# i-ching_2020-06-26_19-34-40.net
KiCad netlist of a schematic drawn in EasyEDA
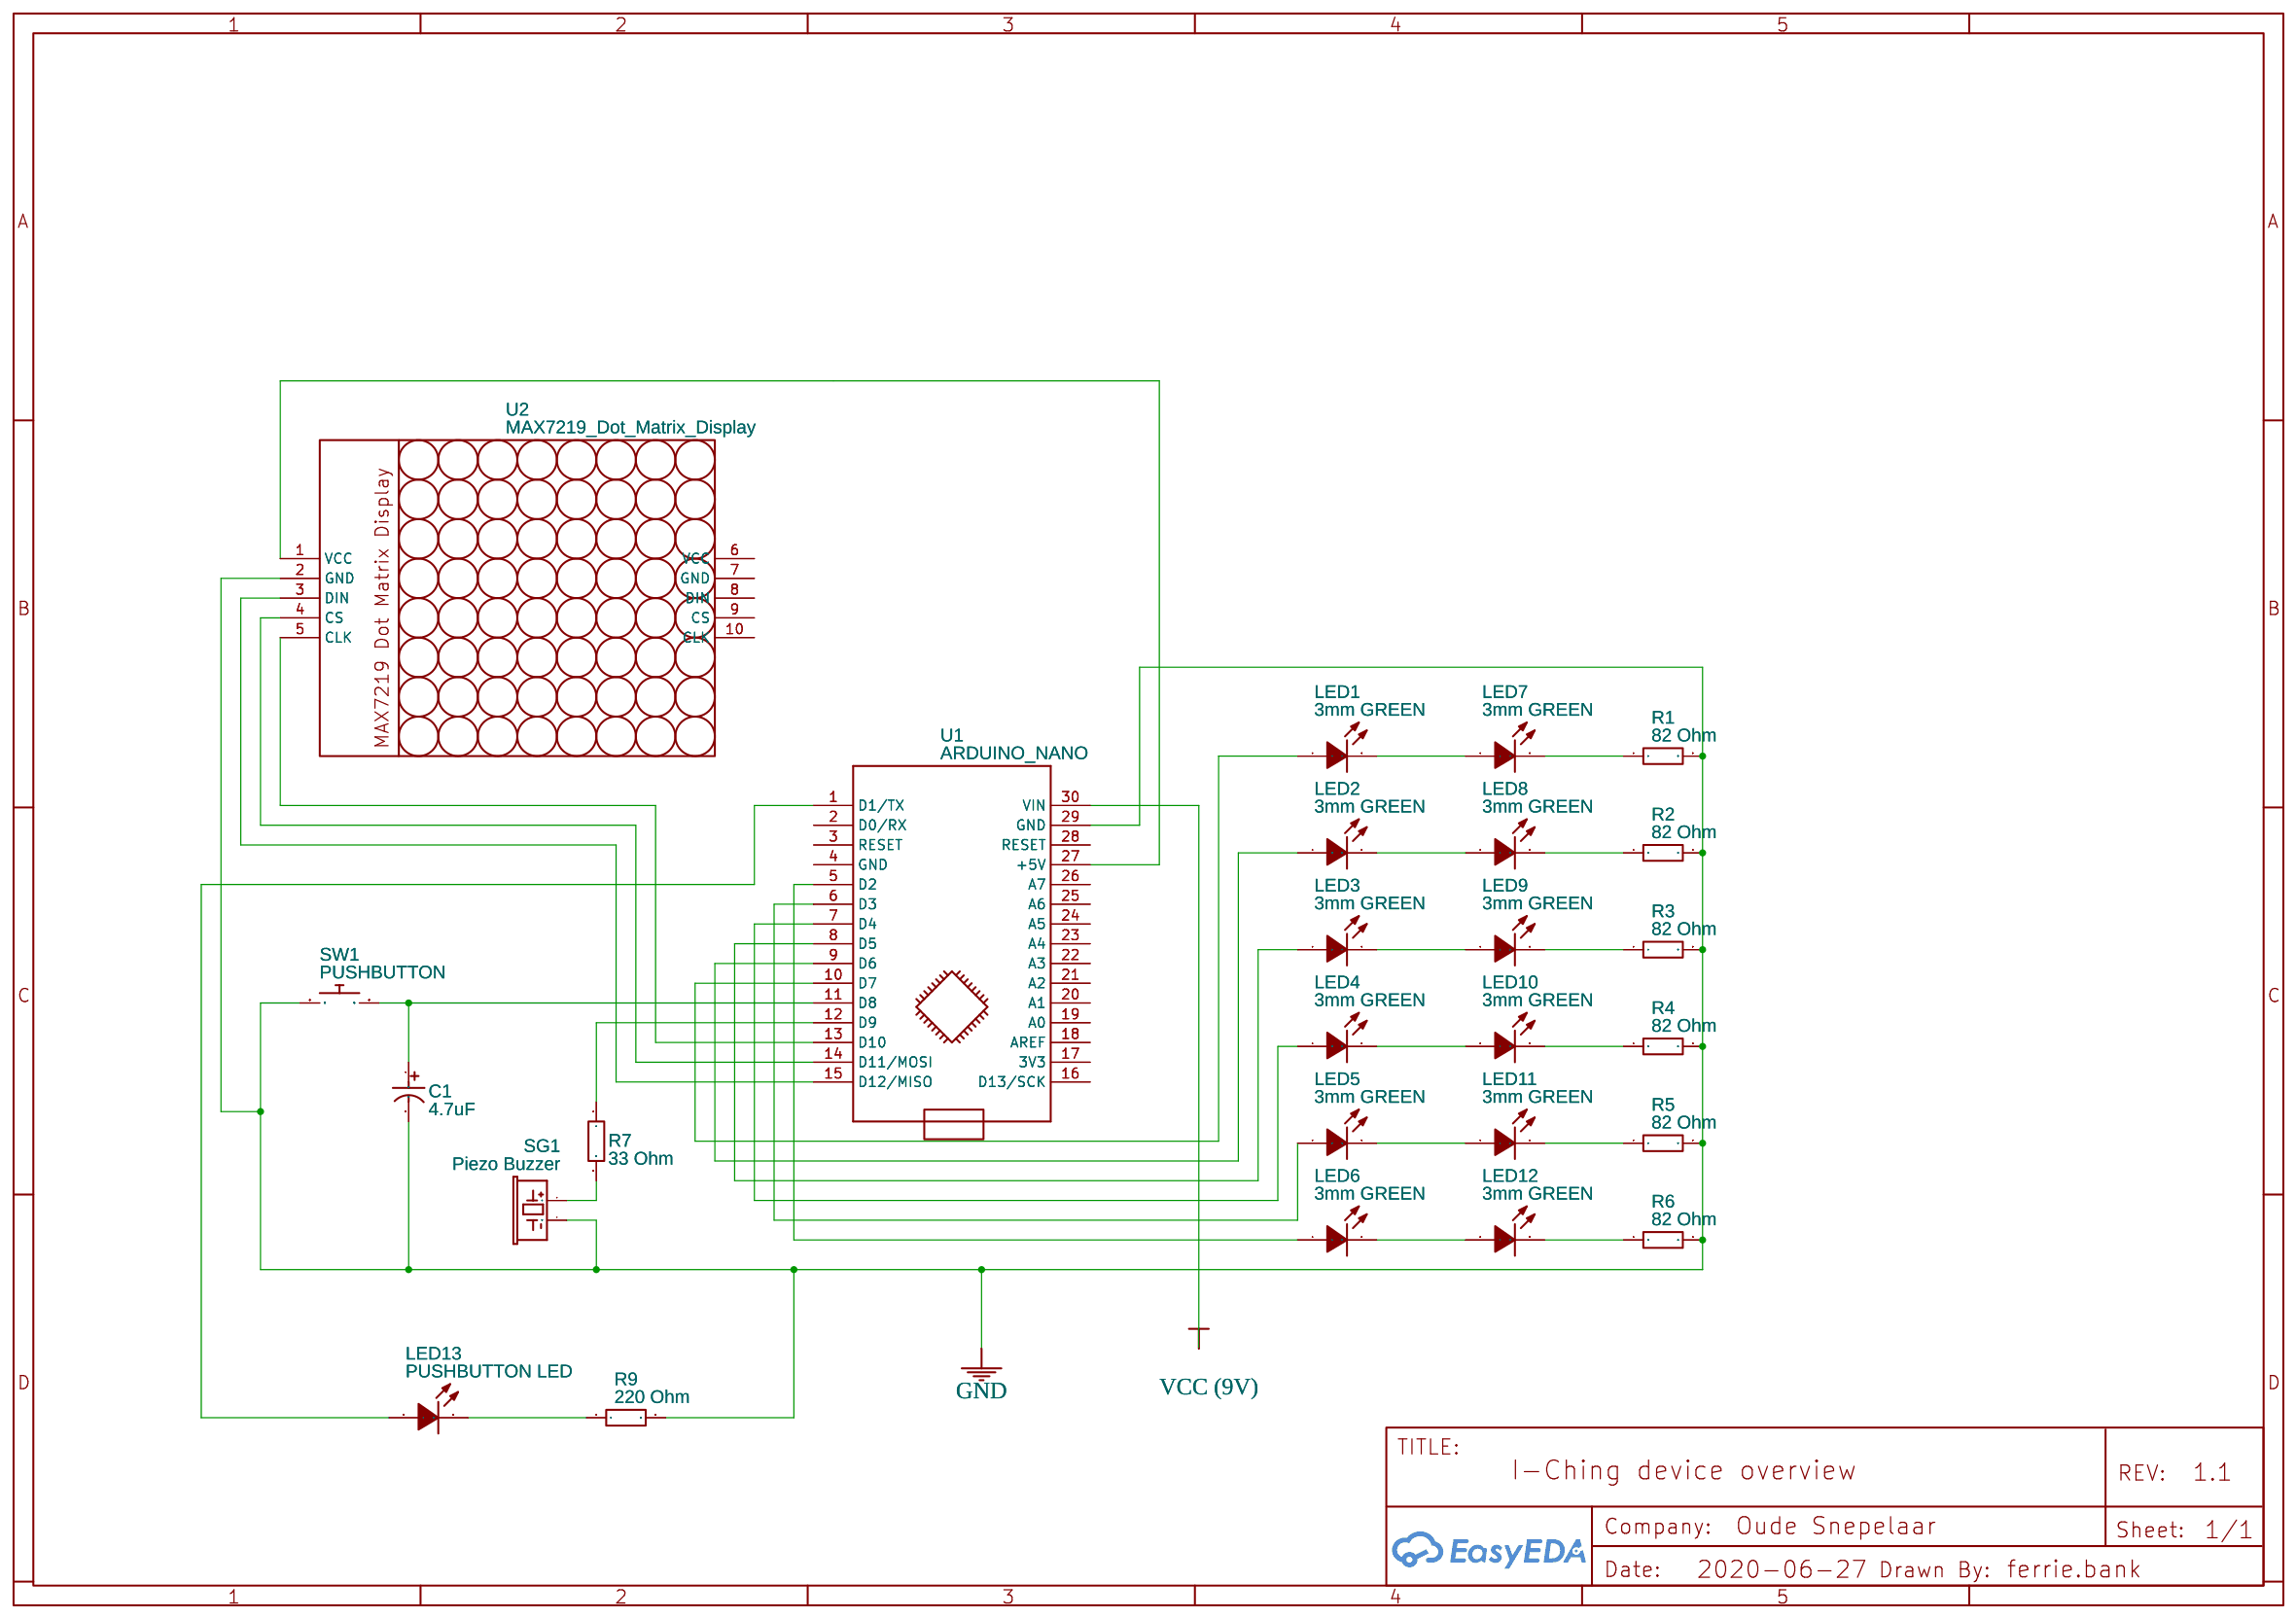
[diagram p0: I-Ching device overview]
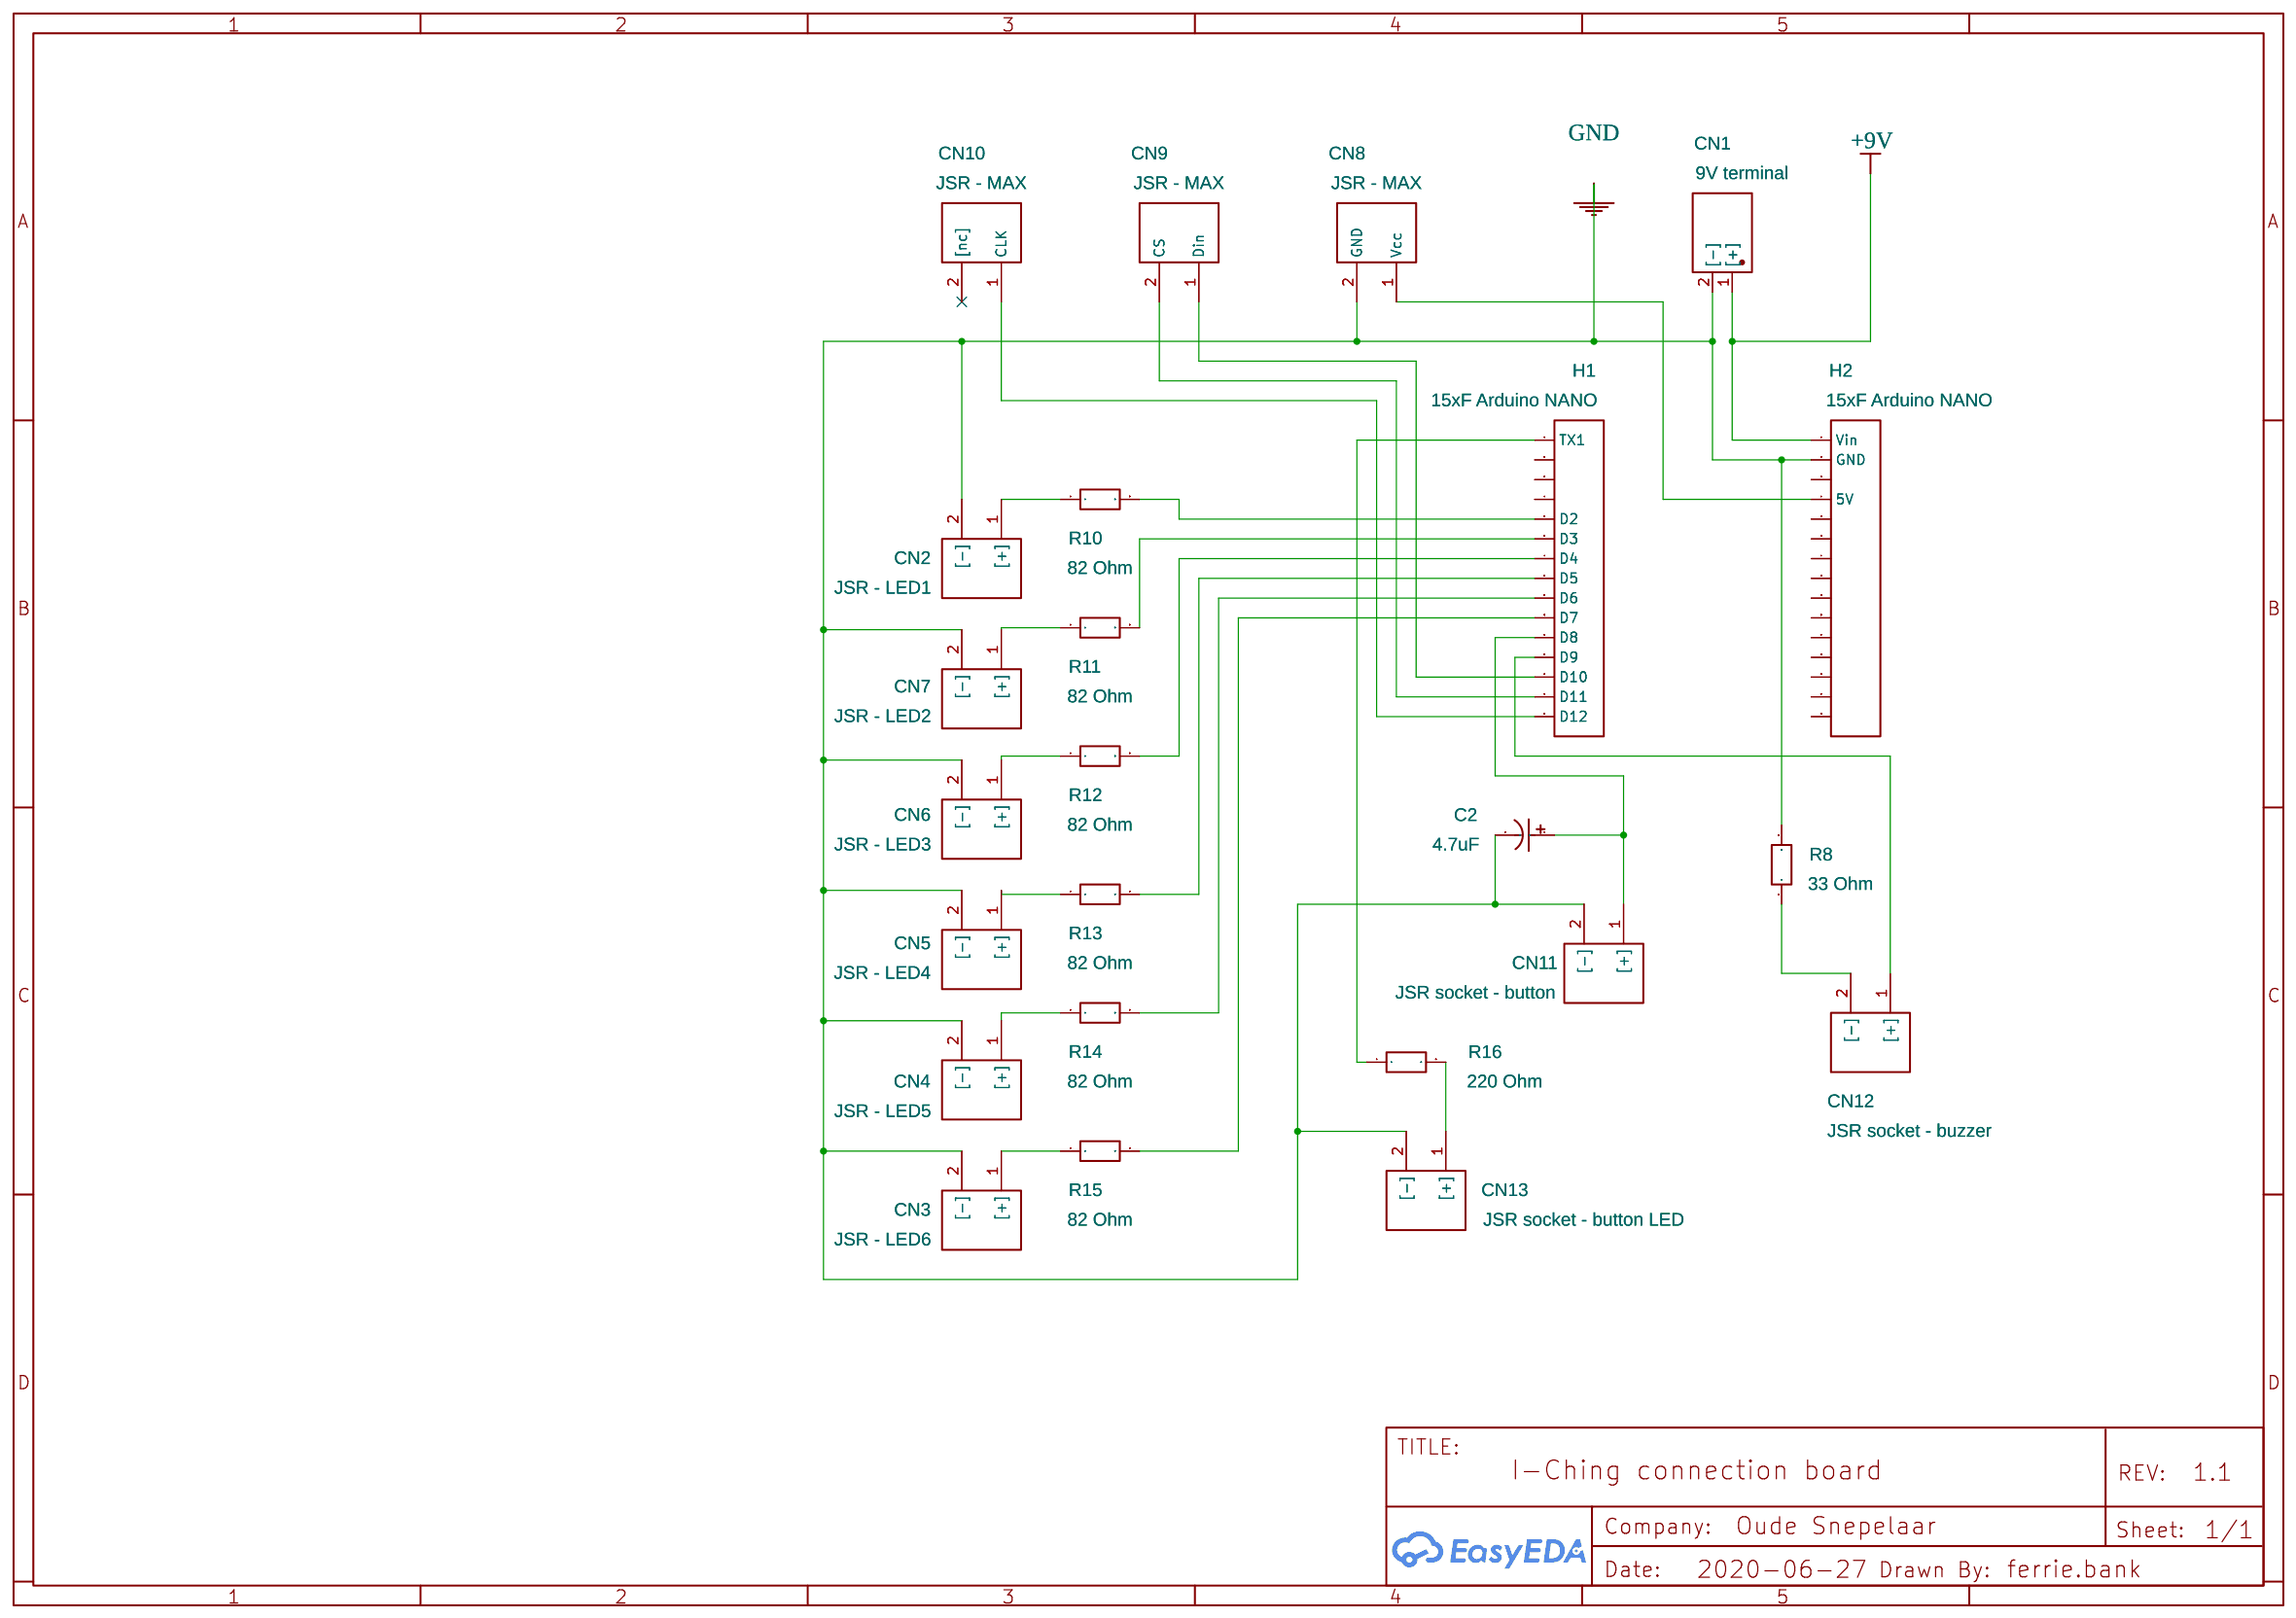
[diagram p1: I-Ching connection board]

(export (version "E")
  (design (tool "Eeschema 10.0.6"))
  (components
    (comp (ref "C1")
      (value "4.7uF")
      (fields (field (name "BOM_Manufacturer Part") "0.1UF 50V") (field (name "BOM_Supplier Part") "C28061"))
      (libsource (lib "") (part "0.1UF 50V"))
    )
    (comp (ref "LED1")
      (value "3mm GREEN")
      (fields (field (name "BOM_Manufacturer Part") "3ARG4HWC") (field (name "BOM_Supplier Part") "C55640"))
      (libsource (lib "") (part "3ARG4HWC"))
    )
    (comp (ref "LED2")
      (value "3mm GREEN")
      (fields (field (name "BOM_Manufacturer Part") "3ARG4HWC") (field (name "BOM_Supplier Part") "C55640"))
      (libsource (lib "") (part "3ARG4HWC"))
    )
    (comp (ref "LED3")
      (value "3mm GREEN")
      (fields (field (name "BOM_Manufacturer Part") "3ARG4HWC") (field (name "BOM_Supplier Part") "C55640"))
      (libsource (lib "") (part "3ARG4HWC"))
    )
    (comp (ref "LED4")
      (value "3mm GREEN")
      (fields (field (name "BOM_Manufacturer Part") "3ARG4HWC") (field (name "BOM_Supplier Part") "C55640"))
      (libsource (lib "") (part "3ARG4HWC"))
    )
    (comp (ref "LED5")
      (value "3mm GREEN")
      (fields (field (name "BOM_Manufacturer Part") "3ARG4HWC") (field (name "BOM_Supplier Part") "C55640"))
      (libsource (lib "") (part "3ARG4HWC"))
    )
    (comp (ref "LED6")
      (value "3mm GREEN")
      (fields (field (name "BOM_Manufacturer Part") "3ARG4HWC") (field (name "BOM_Supplier Part") "C55640"))
      (libsource (lib "") (part "3ARG4HWC"))
    )
    (comp (ref "LED7")
      (value "3mm GREEN")
      (fields (field (name "BOM_Manufacturer Part") "3ARG4HWC") (field (name "BOM_Supplier Part") "C55640"))
      (libsource (lib "") (part "3ARG4HWC"))
    )
    (comp (ref "LED8")
      (value "3mm GREEN")
      (fields (field (name "BOM_Manufacturer Part") "3ARG4HWC") (field (name "BOM_Supplier Part") "C55640"))
      (libsource (lib "") (part "3ARG4HWC"))
    )
    (comp (ref "LED9")
      (value "3mm GREEN")
      (fields (field (name "BOM_Manufacturer Part") "3ARG4HWC") (field (name "BOM_Supplier Part") "C55640"))
      (libsource (lib "") (part "3ARG4HWC"))
    )
    (comp (ref "LED10")
      (value "3mm GREEN")
      (fields (field (name "BOM_Manufacturer Part") "3ARG4HWC") (field (name "BOM_Supplier Part") "C55640"))
      (libsource (lib "") (part "3ARG4HWC"))
    )
    (comp (ref "LED11")
      (value "3mm GREEN")
      (fields (field (name "BOM_Manufacturer Part") "3ARG4HWC") (field (name "BOM_Supplier Part") "C55640"))
      (libsource (lib "") (part "3ARG4HWC"))
    )
    (comp (ref "LED12")
      (value "3mm GREEN")
      (fields (field (name "BOM_Manufacturer Part") "3ARG4HWC") (field (name "BOM_Supplier Part") "C55640"))
      (libsource (lib "") (part "3ARG4HWC"))
    )
    (comp (ref "LED13")
      (value "PUSHBUTTON LED")
      (fields (field (name "BOM_Manufacturer Part") "3ARG4HWC") (field (name "BOM_Supplier Part") "C55640"))
      (libsource (lib "") (part "3ARG4HWC"))
    )
    (comp (ref "R1")
      (value "82 Ohm")
      (fields
        (field (name "BOM_Manufacturer Part") "MFR2WSJT-73-220R")
        (field (name "BOM_Supplier Part") "C176568")
      )
      (libsource (lib "") (part "MFR2WSJT-73-220R_1"))
    )
    (comp (ref "R2")
      (value "82 Ohm")
      (fields
        (field (name "BOM_Manufacturer Part") "MFR2WSJT-73-220R")
        (field (name "BOM_Supplier Part") "C176568")
      )
      (libsource (lib "") (part "MFR2WSJT-73-220R_1"))
    )
    (comp (ref "R3")
      (value "82 Ohm")
      (fields
        (field (name "BOM_Manufacturer Part") "MFR2WSJT-73-220R")
        (field (name "BOM_Supplier Part") "C176568")
      )
      (libsource (lib "") (part "MFR2WSJT-73-220R_1"))
    )
    (comp (ref "R4")
      (value "82 Ohm")
      (fields
        (field (name "BOM_Manufacturer Part") "MFR2WSJT-73-220R")
        (field (name "BOM_Supplier Part") "C176568")
      )
      (libsource (lib "") (part "MFR2WSJT-73-220R_1"))
    )
    (comp (ref "R5")
      (value "82 Ohm")
      (fields
        (field (name "BOM_Manufacturer Part") "MFR2WSJT-73-220R")
        (field (name "BOM_Supplier Part") "C176568")
      )
      (libsource (lib "") (part "MFR2WSJT-73-220R_1"))
    )
    (comp (ref "R6")
      (value "82 Ohm")
      (fields
        (field (name "BOM_Manufacturer Part") "MFR2WSJT-73-220R")
        (field (name "BOM_Supplier Part") "C176568")
      )
      (libsource (lib "") (part "MFR2WSJT-73-220R_1"))
    )
    (comp (ref "R7")
      (value "33 Ohm")
      (fields
        (field (name "BOM_Manufacturer Part") "MFR2WSJT-73-220R")
        (field (name "BOM_Supplier Part") "C176568")
      )
      (libsource (lib "") (part "MFR2WSJT-73-220R"))
    )
    (comp (ref "R9")
      (value "220 Ohm")
      (fields
        (field (name "BOM_Manufacturer Part") "MFR2WSJT-73-220R")
        (field (name "BOM_Supplier Part") "C176568")
      )
      (libsource (lib "") (part "MFR2WSJT-73-220R_1"))
    )
    (comp (ref "SG1") (value "Piezo Buzzer") (libsource (lib "") (part "Piezo Buzzer")))
    (comp (ref "SW1") (value "PUSHBUTTON") (libsource (lib "") (part "SWITCH_PUSHBUTTONCK_KSS")))
    (comp (ref "U1") (value "ARDUINO_NANO") (libsource (lib "") (part "ARDUINO_NANO")))
    (comp (ref "U2")
      (value "MAX7219_Dot_Matrix_Display")
      (libsource (lib "") (part "MAX7219_Dot_Matrix_Display"))
    )
    (comp (ref "C2")
      (value "4.7uF")
      (fields (field (name "BOM_Manufacturer Part") "0.1UF 50V") (field (name "BOM_Supplier Part") "C28061"))
      (libsource (lib "") (part "0.1UF 50V"))
    )
    (comp (ref "CN1")
      (value "9V terminal")
      (fields (field (name "BOM_Manufacturer Part") "PA002-2P") (field (name "BOM_Supplier Part") "C163148"))
      (libsource (lib "") (part "PA002-2P"))
    )
    (comp (ref "CN2")
      (value "JSR - LED1")
      (fields
        (field (name "BOM_Manufacturer Part") "socket.blue5566-2Aneedle")
        (field (name "BOM_Supplier Part") "C62133")
      )
      (libsource (lib "") (part "socket.blue5566-2Aneedle_1"))
    )
    (comp (ref "CN3")
      (value "JSR - LED6")
      (fields
        (field (name "BOM_Manufacturer Part") "socket.blue5566-2Aneedle")
        (field (name "BOM_Supplier Part") "C62133")
      )
      (libsource (lib "") (part "socket.blue5566-2Aneedle_1"))
    )
    (comp (ref "CN4")
      (value "JSR - LED5")
      (fields
        (field (name "BOM_Manufacturer Part") "socket.blue5566-2Aneedle")
        (field (name "BOM_Supplier Part") "C62133")
      )
      (libsource (lib "") (part "socket.blue5566-2Aneedle_1"))
    )
    (comp (ref "CN5")
      (value "JSR - LED4")
      (fields
        (field (name "BOM_Manufacturer Part") "socket.blue5566-2Aneedle")
        (field (name "BOM_Supplier Part") "C62133")
      )
      (libsource (lib "") (part "socket.blue5566-2Aneedle_1"))
    )
    (comp (ref "CN6")
      (value "JSR - LED3")
      (fields
        (field (name "BOM_Manufacturer Part") "socket.blue5566-2Aneedle")
        (field (name "BOM_Supplier Part") "C62133")
      )
      (libsource (lib "") (part "socket.blue5566-2Aneedle_1"))
    )
    (comp (ref "CN7")
      (value "JSR - LED2")
      (fields
        (field (name "BOM_Manufacturer Part") "socket.blue5566-2Aneedle")
        (field (name "BOM_Supplier Part") "C62133")
      )
      (libsource (lib "") (part "socket.blue5566-2Aneedle_1"))
    )
    (comp (ref "CN8")
      (value "JSR - MAX")
      (fields
        (field (name "BOM_Manufacturer Part") "socket.blue5566-2Aneedle")
        (field (name "BOM_Supplier Part") "C62133")
      )
      (libsource (lib "") (part "socket.blue5566-2Aneedle_3"))
    )
    (comp (ref "CN9")
      (value "JSR - MAX")
      (fields
        (field (name "BOM_Manufacturer Part") "socket.blue5566-2Aneedle")
        (field (name "BOM_Supplier Part") "C62133")
      )
      (libsource (lib "") (part "socket.blue5566-2Aneedle_2"))
    )
    (comp (ref "CN10")
      (value "JSR - MAX")
      (fields
        (field (name "BOM_Manufacturer Part") "socket.blue5566-2Aneedle")
        (field (name "BOM_Supplier Part") "C62133")
      )
      (libsource (lib "") (part "socket.blue5566-2Aneedle"))
    )
    (comp (ref "CN11")
      (value "JSR socket - button")
      (fields
        (field (name "BOM_Manufacturer Part") "socket.blue5566-2Aneedle")
        (field (name "BOM_Supplier Part") "C62133")
      )
      (libsource (lib "") (part "socket.blue5566-2Aneedle_1"))
    )
    (comp (ref "CN12")
      (value "JSR socket - buzzer")
      (fields
        (field (name "BOM_Manufacturer Part") "socket.blue5566-2Aneedle")
        (field (name "BOM_Supplier Part") "C62133")
      )
      (libsource (lib "") (part "socket.blue5566-2Aneedle_1"))
    )
    (comp (ref "CN13")
      (value "JSR socket - button LED")
      (fields
        (field (name "BOM_Manufacturer Part") "socket.blue5566-2Aneedle")
        (field (name "BOM_Supplier Part") "C62133")
      )
      (libsource (lib "") (part "socket.blue5566-2Aneedle_1"))
    )
    (comp (ref "H1")
      (value "15xF Arduino NANO")
      (fields
        (field (name "BOM_Manufacturer Part") "220S-1*15P H=8.5MM Ytype Gold-plated")
        (field (name "BOM_Supplier Part") "C124408")
      )
      (libsource (lib "") (part "Header-Female-2.54_1x15"))
    )
    (comp (ref "H2")
      (value "15xF Arduino NANO")
      (fields
        (field (name "BOM_Manufacturer Part") "220S-1*15P H=8.5MM Ytype Gold-plated")
        (field (name "BOM_Supplier Part") "C124408")
      )
      (libsource (lib "") (part "Header-Female-2.54_1x15_1"))
    )
    (comp (ref "R8")
      (value "33 Ohm")
      (fields
        (field (name "BOM_Manufacturer Part") "RN 2WS 1K F T/B A1")
        (field (name "BOM_Supplier Part") "C433624")
      )
      (libsource (lib "") (part "RN 2WS 1K F T/B A1_C433624_1"))
    )
    (comp (ref "R10")
      (value "82 Ohm")
      (fields
        (field (name "BOM_Manufacturer Part") "RN 2WS 1K F T/B A1")
        (field (name "BOM_Supplier Part") "C433624")
      )
      (libsource (lib "") (part "RN 2WS 1K F T/B A1_C433624"))
    )
    (comp (ref "R11")
      (value "82 Ohm")
      (fields
        (field (name "BOM_Manufacturer Part") "RN 2WS 1K F T/B A1")
        (field (name "BOM_Supplier Part") "C433624")
      )
      (libsource (lib "") (part "RN 2WS 1K F T/B A1_C433624"))
    )
    (comp (ref "R12")
      (value "82 Ohm")
      (fields
        (field (name "BOM_Manufacturer Part") "RN 2WS 1K F T/B A1")
        (field (name "BOM_Supplier Part") "C433624")
      )
      (libsource (lib "") (part "RN 2WS 1K F T/B A1_C433624"))
    )
    (comp (ref "R13")
      (value "82 Ohm")
      (fields
        (field (name "BOM_Manufacturer Part") "RN 2WS 1K F T/B A1")
        (field (name "BOM_Supplier Part") "C433624")
      )
      (libsource (lib "") (part "RN 2WS 1K F T/B A1_C433624"))
    )
    (comp (ref "R14")
      (value "82 Ohm")
      (fields
        (field (name "BOM_Manufacturer Part") "RN 2WS 1K F T/B A1")
        (field (name "BOM_Supplier Part") "C433624")
      )
      (libsource (lib "") (part "RN 2WS 1K F T/B A1_C433624"))
    )
    (comp (ref "R15")
      (value "82 Ohm")
      (fields
        (field (name "BOM_Manufacturer Part") "RN 2WS 1K F T/B A1")
        (field (name "BOM_Supplier Part") "C433624")
      )
      (libsource (lib "") (part "RN 2WS 1K F T/B A1_C433624"))
    )
    (comp (ref "R16")
      (value "220 Ohm")
      (fields
        (field (name "BOM_Manufacturer Part") "RN 2WS 1K F T/B A1")
        (field (name "BOM_Supplier Part") "C433624")
      )
      (libsource (lib "") (part "RN 2WS 1K F T/B A1_C433624"))
    )
  )
  (nets
    (net (code "1") (name "+9V") (class "Default")
      (node (ref "CN1") (pin "1") (pinfunction "[+]_1") (pintype "unspecified"))
      (node (ref "H2") (pin "1") (pinfunction "Vin_1") (pintype "unspecified"))
    )
    (net (code "2") (name "GND") (class "Default")
      (node (ref "C1") (pin "2") (pinfunction "2_2") (pintype "input"))
      (node (ref "C2") (pin "2") (pinfunction "2_2") (pintype "input"))
      (node (ref "CN1") (pin "2") (pinfunction "[-]_2") (pintype "unspecified"))
      (node (ref "CN11") (pin "2") (pinfunction "[-]_2") (pintype "unspecified"))
      (node (ref "CN13") (pin "2") (pinfunction "[-]_2") (pintype "unspecified"))
      (node (ref "CN2") (pin "2") (pinfunction "[-]_2") (pintype "unspecified"))
      (node (ref "CN3") (pin "2") (pinfunction "[-]_2") (pintype "unspecified"))
      (node (ref "CN4") (pin "2") (pinfunction "[-]_2") (pintype "unspecified"))
      (node (ref "CN5") (pin "2") (pinfunction "[-]_2") (pintype "unspecified"))
      (node (ref "CN6") (pin "2") (pinfunction "[-]_2") (pintype "unspecified"))
      (node (ref "CN7") (pin "2") (pinfunction "[-]_2") (pintype "unspecified"))
      (node (ref "CN8") (pin "2") (pinfunction "GND_2") (pintype "unspecified"))
      (node (ref "H2") (pin "2") (pinfunction "GND_2") (pintype "unspecified"))
      (node (ref "R1") (pin "2") (pinfunction "2_2") (pintype "input"))
      (node (ref "R2") (pin "2") (pinfunction "2_2") (pintype "input"))
      (node (ref "R3") (pin "2") (pinfunction "2_2") (pintype "input"))
      (node (ref "R4") (pin "2") (pinfunction "2_2") (pintype "input"))
      (node (ref "R5") (pin "2") (pinfunction "2_2") (pintype "input"))
      (node (ref "R6") (pin "2") (pinfunction "2_2") (pintype "input"))
      (node (ref "R8") (pin "2") (pinfunction "2_2") (pintype "unspecified"))
      (node (ref "R9") (pin "2") (pinfunction "2_2") (pintype "input"))
      (node (ref "SG1") (pin "-") (pinfunction "2_-") (pintype "unspecified"))
      (node (ref "SW1") (pin "P$1") (pinfunction "P$1_P$1") (pintype "unspecified"))
      (node (ref "U1") (pin "29") (pinfunction "GND_29") (pintype "unspecified"))
      (node (ref "U2") (pin "2") (pinfunction "GND_2") (pintype "unspecified"))
    )
    (net (code "3") (name "Net-(CN2-[+])") (class "Default")
      (node (ref "CN2") (pin "1") (pinfunction "[+]_1") (pintype "unspecified"))
      (node (ref "R10") (pin "1") (pinfunction "1_1") (pintype "unspecified"))
    )
    (net (code "4") (name "Net-(CN3-[+])") (class "Default")
      (node (ref "CN3") (pin "1") (pinfunction "[+]_1") (pintype "unspecified"))
      (node (ref "R15") (pin "1") (pinfunction "1_1") (pintype "unspecified"))
    )
    (net (code "5") (name "Net-(CN4-[+])") (class "Default")
      (node (ref "CN4") (pin "1") (pinfunction "[+]_1") (pintype "unspecified"))
      (node (ref "R14") (pin "1") (pinfunction "1_1") (pintype "unspecified"))
    )
    (net (code "6") (name "Net-(CN5-[+])") (class "Default")
      (node (ref "CN5") (pin "1") (pinfunction "[+]_1") (pintype "unspecified"))
      (node (ref "R13") (pin "1") (pinfunction "1_1") (pintype "unspecified"))
    )
    (net (code "7") (name "Net-(CN6-[+])") (class "Default")
      (node (ref "CN6") (pin "1") (pinfunction "[+]_1") (pintype "unspecified"))
      (node (ref "R12") (pin "1") (pinfunction "1_1") (pintype "unspecified"))
    )
    (net (code "8") (name "Net-(CN7-[+])") (class "Default")
      (node (ref "CN7") (pin "1") (pinfunction "[+]_1") (pintype "unspecified"))
      (node (ref "R11") (pin "1") (pinfunction "1_1") (pintype "unspecified"))
    )
    (net (code "9") (name "Net-(CN8-Vcc)") (class "Default")
      (node (ref "CN8") (pin "1") (pinfunction "Vcc_1") (pintype "unspecified"))
      (node (ref "H2") (pin "4") (pinfunction "5V_4") (pintype "unspecified"))
    )
    (net (code "10") (name "Net-(CN9-CS)") (class "Default")
      (node (ref "CN9") (pin "2") (pinfunction "CS_2") (pintype "unspecified"))
      (node (ref "H1") (pin "14") (pinfunction "D11_14") (pintype "unspecified"))
    )
    (net (code "11") (name "Net-(CN9-Din)") (class "Default")
      (node (ref "CN9") (pin "1") (pinfunction "Din_1") (pintype "unspecified"))
      (node (ref "H1") (pin "13") (pinfunction "D10_13") (pintype "unspecified"))
    )
    (net (code "12") (name "Net-(CN10-CLK)") (class "Default")
      (node (ref "CN10") (pin "1") (pinfunction "CLK_1") (pintype "unspecified"))
      (node (ref "H1") (pin "15") (pinfunction "D12_15") (pintype "unspecified"))
    )
    (net (code "13") (name "Net-(CN11-[+])") (class "Default")
      (node (ref "C2") (pin "1") (pinfunction "1_1") (pintype "input"))
      (node (ref "CN11") (pin "1") (pinfunction "[+]_1") (pintype "unspecified"))
      (node (ref "H1") (pin "11") (pinfunction "D8_11") (pintype "unspecified"))
    )
    (net (code "14") (name "Net-(CN12-[+])") (class "Default")
      (node (ref "CN12") (pin "1") (pinfunction "[+]_1") (pintype "unspecified"))
      (node (ref "H1") (pin "12") (pinfunction "D9_12") (pintype "unspecified"))
    )
    (net (code "15") (name "Net-(CN12-[-])") (class "Default")
      (node (ref "CN12") (pin "2") (pinfunction "[-]_2") (pintype "unspecified"))
      (node (ref "R8") (pin "1") (pinfunction "1_1") (pintype "unspecified"))
    )
    (net (code "16") (name "Net-(CN13-[+])") (class "Default")
      (node (ref "CN13") (pin "1") (pinfunction "[+]_1") (pintype "unspecified"))
      (node (ref "R16") (pin "2") (pinfunction "2_2") (pintype "unspecified"))
    )
    (net (code "17") (name "Net-(H1-D2)") (class "Default")
      (node (ref "H1") (pin "5") (pinfunction "D2_5") (pintype "unspecified"))
      (node (ref "R10") (pin "2") (pinfunction "2_2") (pintype "unspecified"))
    )
    (net (code "18") (name "Net-(H1-D3)") (class "Default")
      (node (ref "H1") (pin "6") (pinfunction "D3_6") (pintype "unspecified"))
      (node (ref "R11") (pin "2") (pinfunction "2_2") (pintype "unspecified"))
    )
    (net (code "19") (name "Net-(H1-D4)") (class "Default")
      (node (ref "H1") (pin "7") (pinfunction "D4_7") (pintype "unspecified"))
      (node (ref "R12") (pin "2") (pinfunction "2_2") (pintype "unspecified"))
    )
    (net (code "20") (name "Net-(H1-D5)") (class "Default")
      (node (ref "H1") (pin "8") (pinfunction "D5_8") (pintype "unspecified"))
      (node (ref "R13") (pin "2") (pinfunction "2_2") (pintype "unspecified"))
    )
    (net (code "21") (name "Net-(H1-D6)") (class "Default")
      (node (ref "H1") (pin "9") (pinfunction "D6_9") (pintype "unspecified"))
      (node (ref "R14") (pin "2") (pinfunction "2_2") (pintype "unspecified"))
    )
    (net (code "22") (name "Net-(H1-D7)") (class "Default")
      (node (ref "H1") (pin "10") (pinfunction "D7_10") (pintype "unspecified"))
      (node (ref "R15") (pin "2") (pinfunction "2_2") (pintype "unspecified"))
    )
    (net (code "23") (name "Net-(H1-TX1)") (class "Default")
      (node (ref "H1") (pin "1") (pinfunction "TX1_1") (pintype "unspecified"))
      (node (ref "R16") (pin "1") (pinfunction "1_1") (pintype "unspecified"))
    )
    (net (code "24") (name "Net-(LED1-A)") (class "Default")
      (node (ref "LED1") (pin "1") (pinfunction "A_1") (pintype "unspecified"))
      (node (ref "U1") (pin "10") (pinfunction "D7_10") (pintype "unspecified"))
    )
    (net (code "25") (name "Net-(LED1-K)") (class "Default")
      (node (ref "LED1") (pin "2") (pinfunction "K_2") (pintype "unspecified"))
      (node (ref "LED7") (pin "1") (pinfunction "A_1") (pintype "unspecified"))
    )
    (net (code "26") (name "Net-(LED2-A)") (class "Default")
      (node (ref "LED2") (pin "1") (pinfunction "A_1") (pintype "unspecified"))
      (node (ref "U1") (pin "9") (pinfunction "D6_9") (pintype "unspecified"))
    )
    (net (code "27") (name "Net-(LED2-K)") (class "Default")
      (node (ref "LED2") (pin "2") (pinfunction "K_2") (pintype "unspecified"))
      (node (ref "LED8") (pin "1") (pinfunction "A_1") (pintype "unspecified"))
    )
    (net (code "28") (name "Net-(LED3-A)") (class "Default")
      (node (ref "LED3") (pin "1") (pinfunction "A_1") (pintype "unspecified"))
      (node (ref "U1") (pin "8") (pinfunction "D5_8") (pintype "unspecified"))
    )
    (net (code "29") (name "Net-(LED3-K)") (class "Default")
      (node (ref "LED3") (pin "2") (pinfunction "K_2") (pintype "unspecified"))
      (node (ref "LED9") (pin "1") (pinfunction "A_1") (pintype "unspecified"))
    )
    (net (code "30") (name "Net-(LED4-A)") (class "Default")
      (node (ref "LED4") (pin "1") (pinfunction "A_1") (pintype "unspecified"))
      (node (ref "U1") (pin "7") (pinfunction "D4_7") (pintype "unspecified"))
    )
    (net (code "31") (name "Net-(LED5-A)") (class "Default")
      (node (ref "LED5") (pin "1") (pinfunction "A_1") (pintype "unspecified"))
      (node (ref "U1") (pin "6") (pinfunction "D3_6") (pintype "unspecified"))
    )
    (net (code "32") (name "Net-(LED6-A)") (class "Default")
      (node (ref "LED6") (pin "1") (pinfunction "A_1") (pintype "unspecified"))
      (node (ref "U1") (pin "5") (pinfunction "D2_5") (pintype "unspecified"))
    )
    (net (code "33") (name "Net-(LED7-K)") (class "Default")
      (node (ref "LED7") (pin "2") (pinfunction "K_2") (pintype "unspecified"))
      (node (ref "R1") (pin "1") (pinfunction "1_1") (pintype "input"))
    )
    (net (code "34") (name "Net-(LED8-K)") (class "Default")
      (node (ref "LED8") (pin "2") (pinfunction "K_2") (pintype "unspecified"))
      (node (ref "R2") (pin "1") (pinfunction "1_1") (pintype "input"))
    )
    (net (code "35") (name "Net-(LED9-K)") (class "Default")
      (node (ref "LED9") (pin "2") (pinfunction "K_2") (pintype "unspecified"))
      (node (ref "R3") (pin "1") (pinfunction "1_1") (pintype "input"))
    )
    (net (code "36") (name "Net-(LED10-A)") (class "Default")
      (node (ref "LED10") (pin "1") (pinfunction "A_1") (pintype "unspecified"))
      (node (ref "LED4") (pin "2") (pinfunction "K_2") (pintype "unspecified"))
    )
    (net (code "37") (name "Net-(LED10-K)") (class "Default")
      (node (ref "LED10") (pin "2") (pinfunction "K_2") (pintype "unspecified"))
      (node (ref "R4") (pin "1") (pinfunction "1_1") (pintype "input"))
    )
    (net (code "38") (name "Net-(LED11-A)") (class "Default")
      (node (ref "LED11") (pin "1") (pinfunction "A_1") (pintype "unspecified"))
      (node (ref "LED5") (pin "2") (pinfunction "K_2") (pintype "unspecified"))
    )
    (net (code "39") (name "Net-(LED11-K)") (class "Default")
      (node (ref "LED11") (pin "2") (pinfunction "K_2") (pintype "unspecified"))
      (node (ref "R5") (pin "1") (pinfunction "1_1") (pintype "input"))
    )
    (net (code "40") (name "Net-(LED12-A)") (class "Default")
      (node (ref "LED12") (pin "1") (pinfunction "A_1") (pintype "unspecified"))
      (node (ref "LED6") (pin "2") (pinfunction "K_2") (pintype "unspecified"))
    )
    (net (code "41") (name "Net-(LED12-K)") (class "Default")
      (node (ref "LED12") (pin "2") (pinfunction "K_2") (pintype "unspecified"))
      (node (ref "R6") (pin "1") (pinfunction "1_1") (pintype "input"))
    )
    (net (code "42") (name "Net-(LED13-A)") (class "Default")
      (node (ref "LED13") (pin "1") (pinfunction "A_1") (pintype "unspecified"))
      (node (ref "U1") (pin "1") (pinfunction "D1/TX_1") (pintype "unspecified"))
    )
    (net (code "43") (name "Net-(LED13-K)") (class "Default")
      (node (ref "LED13") (pin "2") (pinfunction "K_2") (pintype "unspecified"))
      (node (ref "R9") (pin "1") (pinfunction "1_1") (pintype "input"))
    )
    (net (code "44") (name "Net-(SG1-1)") (class "Default")
      (node (ref "R7") (pin "2") (pinfunction "2_2") (pintype "input"))
      (node (ref "SG1") (pin "+") (pinfunction "1_+") (pintype "unspecified"))
    )
    (net (code "45") (name "Net-(U1-+5V)") (class "Default")
      (node (ref "U1") (pin "27") (pinfunction "+5V_27") (pintype "unspecified"))
      (node (ref "U2") (pin "1") (pinfunction "VCC_1") (pintype "unspecified"))
    )
    (net (code "46") (name "Net-(U1-D8)") (class "Default")
      (node (ref "C1") (pin "1") (pinfunction "1_1") (pintype "input"))
      (node (ref "SW1") (pin "P$2") (pinfunction "P$2_P$2") (pintype "unspecified"))
      (node (ref "U1") (pin "11") (pinfunction "D8_11") (pintype "unspecified"))
    )
    (net (code "47") (name "Net-(U1-D9)") (class "Default")
      (node (ref "R7") (pin "1") (pinfunction "1_1") (pintype "input"))
      (node (ref "U1") (pin "12") (pinfunction "D9_12") (pintype "unspecified"))
    )
    (net (code "48") (name "Net-(U1-D10)") (class "Default")
      (node (ref "U1") (pin "13") (pinfunction "D10_13") (pintype "unspecified"))
      (node (ref "U2") (pin "5") (pinfunction "CLK_5") (pintype "unspecified"))
    )
    (net (code "49") (name "Net-(U1-D11{slash}MOSI)") (class "Default")
      (node (ref "U1") (pin "14") (pinfunction "D11/MOSI_14") (pintype "unspecified"))
      (node (ref "U2") (pin "4") (pinfunction "CS_4") (pintype "unspecified"))
    )
    (net (code "50") (name "Net-(U1-D12{slash}MISO)") (class "Default")
      (node (ref "U1") (pin "15") (pinfunction "D12/MISO_15") (pintype "unspecified"))
      (node (ref "U2") (pin "3") (pinfunction "DIN_3") (pintype "unspecified"))
    )
    (net (code "51") (name "VCC (9V)") (class "Default")
      (node (ref "U1") (pin "30") (pinfunction "VIN_30") (pintype "unspecified"))
    )
    (net (code "52") (name "unconnected-(CN10-[nc]-Pad2)") (class "Default")
      (node (ref "CN10") (pin "2") (pinfunction "[nc]_2") (pintype "unspecified+no_connect"))
    )
    (net (code "53") (name "unconnected-(H1-Pad2)") (class "Default")
      (node (ref "H1") (pin "2") (pintype "unspecified"))
    )
    (net (code "54") (name "unconnected-(H1-Pad3)") (class "Default")
      (node (ref "H1") (pin "3") (pintype "unspecified"))
    )
    (net (code "55") (name "unconnected-(H1-Pad4)") (class "Default")
      (node (ref "H1") (pin "4") (pintype "unspecified"))
    )
    (net (code "56") (name "unconnected-(H2-Pad3)") (class "Default")
      (node (ref "H2") (pin "3") (pintype "unspecified"))
    )
    (net (code "57") (name "unconnected-(H2-Pad5)") (class "Default")
      (node (ref "H2") (pin "5") (pintype "unspecified"))
    )
    (net (code "58") (name "unconnected-(H2-Pad6)") (class "Default")
      (node (ref "H2") (pin "6") (pintype "unspecified"))
    )
    (net (code "59") (name "unconnected-(H2-Pad7)") (class "Default")
      (node (ref "H2") (pin "7") (pintype "unspecified"))
    )
    (net (code "60") (name "unconnected-(H2-Pad8)") (class "Default")
      (node (ref "H2") (pin "8") (pintype "unspecified"))
    )
    (net (code "61") (name "unconnected-(H2-Pad9)") (class "Default")
      (node (ref "H2") (pin "9") (pintype "unspecified"))
    )
    (net (code "62") (name "unconnected-(H2-Pad10)") (class "Default")
      (node (ref "H2") (pin "10") (pintype "unspecified"))
    )
    (net (code "63") (name "unconnected-(H2-Pad11)") (class "Default")
      (node (ref "H2") (pin "11") (pintype "unspecified"))
    )
    (net (code "64") (name "unconnected-(H2-Pad12)") (class "Default")
      (node (ref "H2") (pin "12") (pintype "unspecified"))
    )
    (net (code "65") (name "unconnected-(H2-Pad13)") (class "Default")
      (node (ref "H2") (pin "13") (pintype "unspecified"))
    )
    (net (code "66") (name "unconnected-(H2-Pad14)") (class "Default")
      (node (ref "H2") (pin "14") (pintype "unspecified"))
    )
    (net (code "67") (name "unconnected-(H2-Pad15)") (class "Default")
      (node (ref "H2") (pin "15") (pintype "unspecified"))
    )
    (net (code "68") (name "unconnected-(U1-3V3-Pad17)") (class "Default")
      (node (ref "U1") (pin "17") (pinfunction "3V3_17") (pintype "unspecified"))
    )
    (net (code "69") (name "unconnected-(U1-A0-Pad19)") (class "Default")
      (node (ref "U1") (pin "19") (pinfunction "A0_19") (pintype "unspecified"))
    )
    (net (code "70") (name "unconnected-(U1-A1-Pad20)") (class "Default")
      (node (ref "U1") (pin "20") (pinfunction "A1_20") (pintype "unspecified"))
    )
    (net (code "71") (name "unconnected-(U1-A2-Pad21)") (class "Default")
      (node (ref "U1") (pin "21") (pinfunction "A2_21") (pintype "unspecified"))
    )
    (net (code "72") (name "unconnected-(U1-A3-Pad22)") (class "Default")
      (node (ref "U1") (pin "22") (pinfunction "A3_22") (pintype "unspecified"))
    )
    (net (code "73") (name "unconnected-(U1-A4-Pad23)") (class "Default")
      (node (ref "U1") (pin "23") (pinfunction "A4_23") (pintype "unspecified"))
    )
    (net (code "74") (name "unconnected-(U1-A5-Pad24)") (class "Default")
      (node (ref "U1") (pin "24") (pinfunction "A5_24") (pintype "unspecified"))
    )
    (net (code "75") (name "unconnected-(U1-A6-Pad25)") (class "Default")
      (node (ref "U1") (pin "25") (pinfunction "A6_25") (pintype "unspecified"))
    )
    (net (code "76") (name "unconnected-(U1-A7-Pad26)") (class "Default")
      (node (ref "U1") (pin "26") (pinfunction "A7_26") (pintype "unspecified"))
    )
    (net (code "77") (name "unconnected-(U1-AREF-Pad18)") (class "Default")
      (node (ref "U1") (pin "18") (pinfunction "AREF_18") (pintype "unspecified"))
    )
    (net (code "78") (name "unconnected-(U1-D0{slash}RX-Pad2)") (class "Default")
      (node (ref "U1") (pin "2") (pinfunction "D0/RX_2") (pintype "unspecified"))
    )
    (net (code "79") (name "unconnected-(U1-D13{slash}SCK-Pad16)") (class "Default")
      (node (ref "U1") (pin "16") (pinfunction "D13/SCK_16") (pintype "unspecified"))
    )
    (net (code "80") (name "unconnected-(U1-GND-Pad4)") (class "Default")
      (node (ref "U1") (pin "4") (pinfunction "GND_4") (pintype "unspecified"))
    )
    (net (code "81") (name "unconnected-(U1-RESET-Pad3)") (class "Default")
      (node (ref "U1") (pin "3") (pinfunction "RESET_3") (pintype "unspecified"))
    )
    (net (code "82") (name "unconnected-(U1-RESET-Pad28)") (class "Default")
      (node (ref "U1") (pin "28") (pinfunction "RESET_28") (pintype "unspecified"))
    )
    (net (code "83") (name "unconnected-(U2-CLK-Pad10)") (class "Default")
      (node (ref "U2") (pin "10") (pinfunction "CLK_10") (pintype "unspecified"))
    )
    (net (code "84") (name "unconnected-(U2-CS-Pad9)") (class "Default")
      (node (ref "U2") (pin "9") (pinfunction "CS_9") (pintype "unspecified"))
    )
    (net (code "85") (name "unconnected-(U2-DIN-Pad8)") (class "Default")
      (node (ref "U2") (pin "8") (pinfunction "DIN_8") (pintype "unspecified"))
    )
    (net (code "86") (name "unconnected-(U2-GND-Pad7)") (class "Default")
      (node (ref "U2") (pin "7") (pinfunction "GND_7") (pintype "unspecified"))
    )
    (net (code "87") (name "unconnected-(U2-VCC-Pad6)") (class "Default")
      (node (ref "U2") (pin "6") (pinfunction "VCC_6") (pintype "unspecified"))
    )
  )
)
